# ESP32CAM-Motorhat.net
KiCad netlist of a schematic drawn in EAGLE
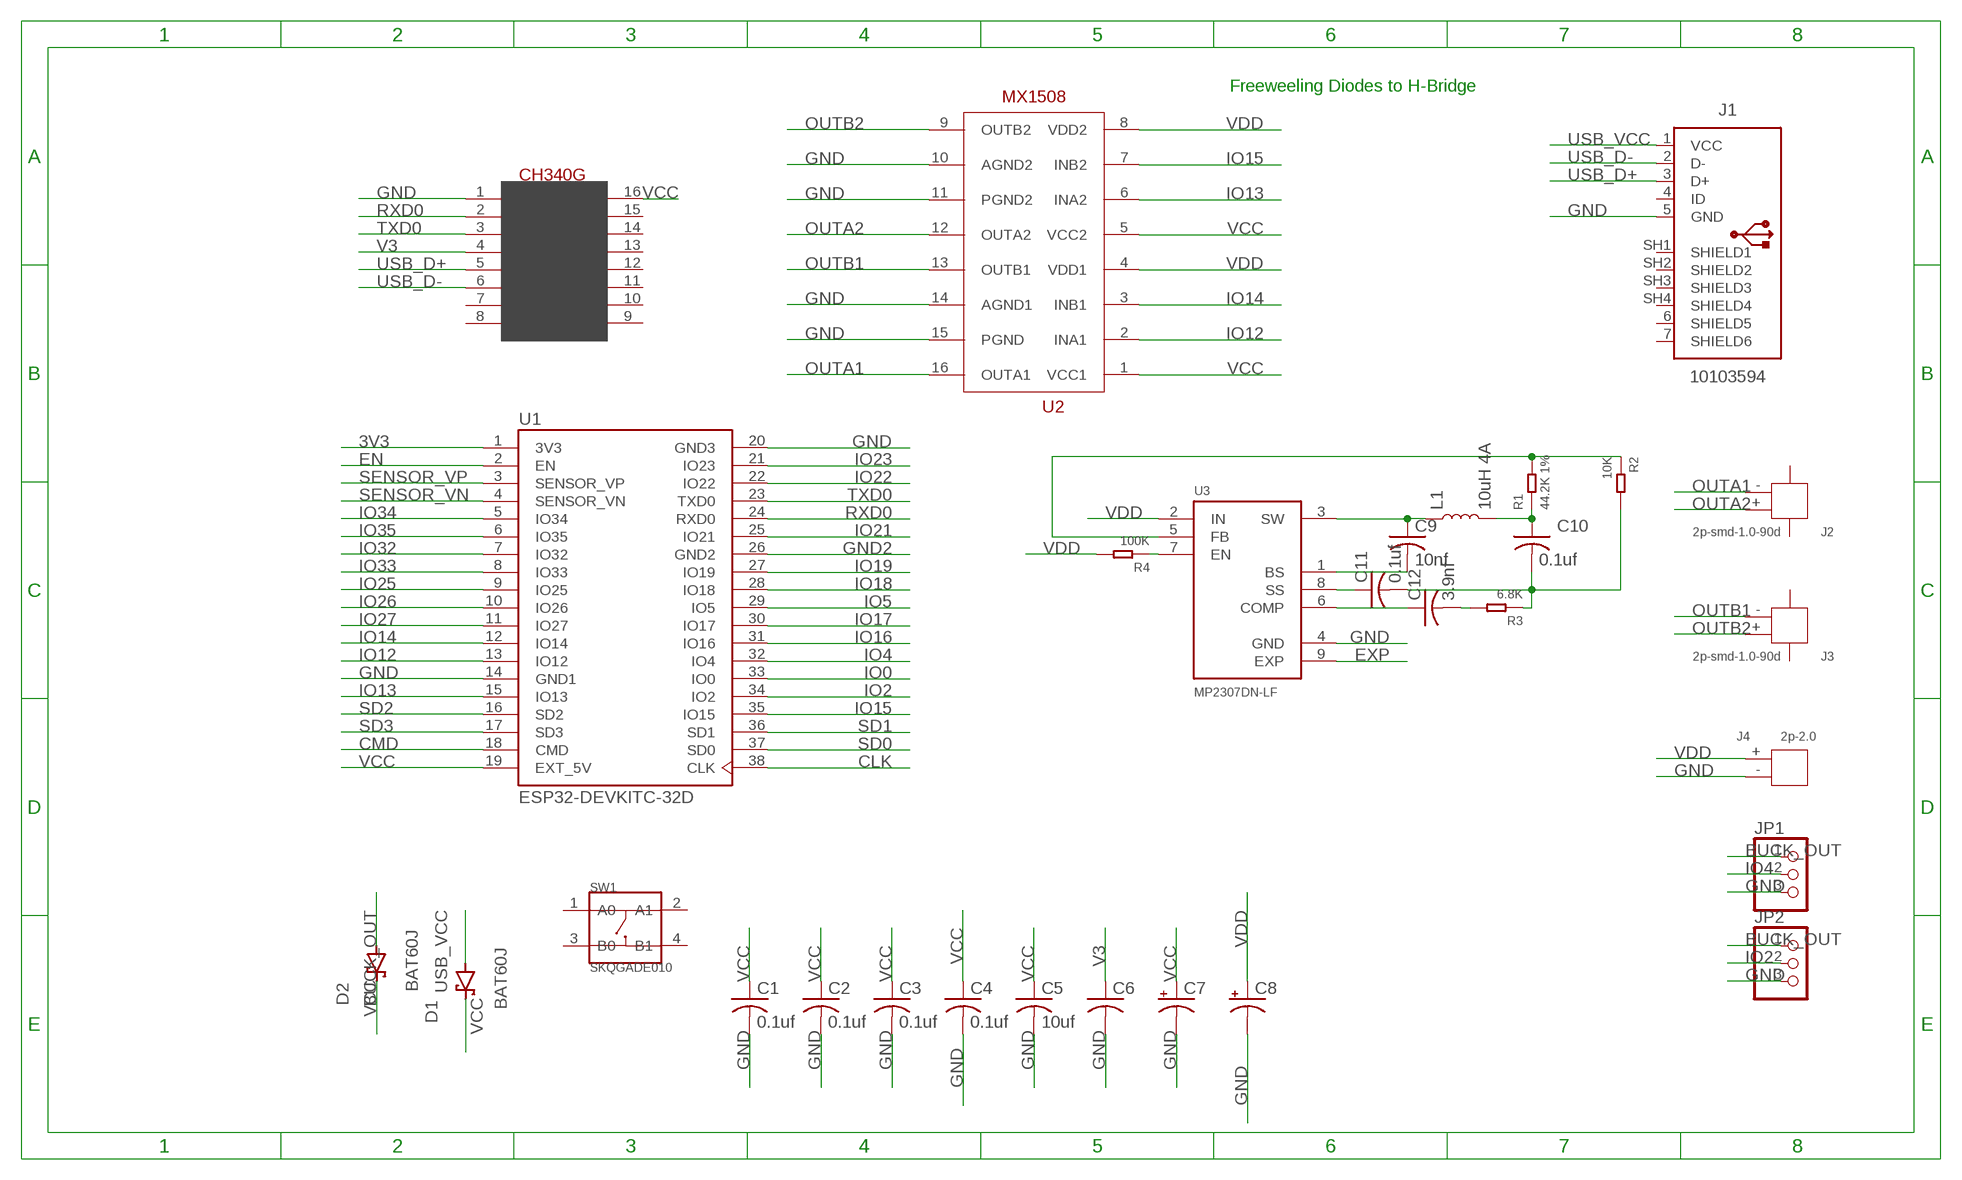
[diagram p0: schematic, sheet 1]

(export (version "E")
  (design (tool "Eeschema 10.0.6"))
  (components
    (comp (ref "C1")
      (value "0.1uf")
      (footprint "eagle-import:C1206")
      (libsource (lib "eagle-import") (part "C-USC1206"))
    )
    (comp (ref "C2")
      (value "0.1uf")
      (footprint "eagle-import:C1206")
      (libsource (lib "eagle-import") (part "C-USC1206"))
    )
    (comp (ref "C3")
      (value "0.1uf")
      (footprint "eagle-import:C1206")
      (libsource (lib "eagle-import") (part "C-USC1206"))
    )
    (comp (ref "C4")
      (value "0.1uf")
      (footprint "eagle-import:C1206")
      (libsource (lib "eagle-import") (part "C-USC1206"))
    )
    (comp (ref "C5")
      (value "10uf")
      (footprint "eagle-import:C1206")
      (libsource (lib "eagle-import") (part "C-USC1206"))
    )
    (comp (ref "C6")
      (value "C-USC1206")
      (footprint "eagle-import:C1206")
      (libsource (lib "eagle-import") (part "C-USC1206"))
    )
    (comp (ref "C7")
      (value "CPOL-USD")
      (footprint "eagle-import:PANASONIC_D")
      (libsource (lib "eagle-import") (part "CPOL-USD"))
    )
    (comp (ref "C8")
      (value "CPOL-USD")
      (footprint "eagle-import:PANASONIC_D")
      (libsource (lib "eagle-import") (part "CPOL-USD"))
    )
    (comp (ref "C9")
      (value "10nf")
      (footprint "eagle-import:C1206")
      (libsource (lib "eagle-import") (part "C-USC1206"))
    )
    (comp (ref "C10")
      (value "0.1uf")
      (footprint "eagle-import:C1206")
      (libsource (lib "eagle-import") (part "C-USC1206"))
    )
    (comp (ref "C11")
      (value "0.1uf")
      (footprint "eagle-import:C1206")
      (libsource (lib "eagle-import") (part "C-USC1206"))
    )
    (comp (ref "C12")
      (value "3.9nf")
      (footprint "eagle-import:C1206")
      (libsource (lib "eagle-import") (part "C-USC1206"))
    )
    (comp (ref "D1")
      (value "BAT60J")
      (footprint "eagle-import:SOD323_ST")
      (libsource (lib "eagle-import") (part "BAT60J"))
    )
    (comp (ref "D2")
      (value "BAT60J")
      (footprint "eagle-import:SOD323_ST")
      (libsource (lib "eagle-import") (part "BAT60J"))
    )
    (comp (ref "J1")
      (value "10103594")
      (footprint "eagle-import:10103594")
      (fields (field (name "MANUFACTURER") "Amphenol ICC (FCI)") (field (name "MPN") "10103594-0001LF"))
      (libsource (lib "eagle-import") (part "10103594"))
    )
    (comp (ref "J2")
      (value "2p-smd-1.0-90d")
      (footprint "eagle-import:HW2-SMD-1.0-90D")
      (libsource (lib "eagle-import") (part "SMD-JST-2P-1.0-90D"))
    )
    (comp (ref "J3")
      (value "2p-smd-1.0-90d")
      (footprint "eagle-import:HW2-SMD-1.0-90D")
      (libsource (lib "eagle-import") (part "SMD-JST-2P-1.0-90D"))
    )
    (comp (ref "J4")
      (value "2p-2.0")
      (footprint "eagle-import:H2-2.0-6X4.5MM")
      (fields (field (name "SPICEPREFIX") "B"))
      (libsource (lib "eagle-import") (part "DIP-JST-2P-2.0"))
    )
    (comp (ref "JP1")
      (value "PINHD-1X3CB")
      (footprint "eagle-import:1X03-CLEANBIG")
      (libsource (lib "eagle-import") (part "PINHD-1X3CB"))
    )
    (comp (ref "JP2")
      (value "PINHD-1X3CB")
      (footprint "eagle-import:1X03-CLEANBIG")
      (libsource (lib "eagle-import") (part "PINHD-1X3CB"))
    )
    (comp (ref "L1")
      (value "10uH 4A")
      (footprint "eagle-import:0402_MURATA")
      (libsource (lib "eagle-import") (part "19NH-0402"))
    )
    (comp (ref "R1")
      (value "44.2K 1%")
      (footprint "eagle-import:R0805")
      (fields (field (name "MPN") "RC0805JR-071KL"))
      (libsource (lib "eagle-import") (part "SMD-RES-0R-1%-1/8W(0805)"))
    )
    (comp (ref "R2")
      (value "10K")
      (footprint "eagle-import:R0805")
      (fields (field (name "MPN") "RC0805JR-071KL"))
      (libsource (lib "eagle-import") (part "SMD-RES-0R-1%-1/8W(0805)"))
    )
    (comp (ref "R3")
      (value "6.8K")
      (footprint "eagle-import:R0805")
      (fields (field (name "MPN") "RC0805JR-071KL"))
      (libsource (lib "eagle-import") (part "SMD-RES-0R-1%-1/8W(0805)"))
    )
    (comp (ref "R4")
      (value "100K")
      (footprint "eagle-import:R0805")
      (fields (field (name "MPN") "RC0805JR-071KL"))
      (libsource (lib "eagle-import") (part "SMD-RES-0R-1%-1/8W(0805)"))
    )
    (comp (ref "SW1")
      (value "SKQGADE010")
      (footprint "eagle-import:SW4-SMD-5.2X5.2X1.5MM")
      (libsource (lib "eagle-import") (part "SMD-BUTTON(4P-5.2X5.2X1.5MM-SKQGADE010)-SKQGADE010"))
    )
    (comp (ref "U1")
      (value "ESP32-DEVKITC-32D")
      (footprint "eagle-import:MODULE_ESP32-DEVKITC-32D")
      (fields (field (name "MF") "Espressif Systems"))
      (libsource (lib "eagle-import") (part "ESP32-DEVKITC-32D"))
    )
    (comp (ref "U2")
      (value "MX1508")
      (footprint "eagle-import:SOP-16")
      (fields (field (name "MF") "Sinotech Mixic Electronics Co., Ltd"))
      (libsource (lib "eagle-import") (part "MX1508"))
    )
    (comp (ref "U3")
      (value "MP2307DN-LF")
      (footprint "eagle-import:SOIC127P600X170-9N")
      (fields (field (name "MF") "Monolithic Power"))
      (libsource (lib "eagle-import") (part "MP2307DN-LF"))
    )
    (comp (ref "U4")
      (value "CH340G")
      (footprint "eagle-import:SOIC16")
      (libsource (lib "eagle-import") (part "CH340G"))
    )
  )
  (nets
    (net (code "1") (name "/3V3") (class "Default")
      (node (ref "U1") (pin "1") (pinfunction "3V3_1") (pintype "power_in"))
    )
    (net (code "2") (name "/BUCK_OUT") (class "Default")
      (node (ref "C10") (pin "1") (pinfunction "1_1") (pintype "passive"))
      (node (ref "D2") (pin "A") (pinfunction "A_A") (pintype "passive"))
      (node (ref "JP1") (pin "1") (pinfunction "1_1") (pintype "passive"))
      (node (ref "JP2") (pin "1") (pinfunction "1_1") (pintype "passive"))
      (node (ref "L1") (pin "P$2") (pinfunction "2_P$2") (pintype "passive"))
      (node (ref "R1") (pin "1") (pinfunction "1_1") (pintype "passive"))
    )
    (net (code "3") (name "/CLK") (class "Default")
      (node (ref "U1") (pin "38") (pinfunction "CLK_38") (pintype "input"))
    )
    (net (code "4") (name "/CMD") (class "Default")
      (node (ref "U1") (pin "18") (pinfunction "CMD_18") (pintype "bidirectional"))
    )
    (net (code "5") (name "/EN") (class "Default")
      (node (ref "U1") (pin "2") (pinfunction "EN_2") (pintype "input"))
    )
    (net (code "6") (name "/EXP") (class "Default")
      (node (ref "U3") (pin "9") (pinfunction "EXP_9") (pintype "power_in"))
    )
    (net (code "7") (name "/GND") (class "Default")
      (node (ref "C1") (pin "2") (pinfunction "2_2") (pintype "passive"))
      (node (ref "C2") (pin "2") (pinfunction "2_2") (pintype "passive"))
      (node (ref "C3") (pin "2") (pinfunction "2_2") (pintype "passive"))
      (node (ref "C4") (pin "2") (pinfunction "2_2") (pintype "passive"))
      (node (ref "C5") (pin "2") (pinfunction "2_2") (pintype "passive"))
      (node (ref "C6") (pin "2") (pinfunction "2_2") (pintype "passive"))
      (node (ref "C7") (pin "-") (pinfunction "-_-") (pintype "passive"))
      (node (ref "C8") (pin "-") (pinfunction "-_-") (pintype "passive"))
      (node (ref "J1") (pin "5") (pinfunction "GND_5") (pintype "power_in"))
      (node (ref "J4") (pin "-") (pinfunction "P$2_-") (pintype "bidirectional"))
      (node (ref "JP1") (pin "3") (pinfunction "3_3") (pintype "passive"))
      (node (ref "JP2") (pin "3") (pinfunction "3_3") (pintype "passive"))
      (node (ref "U1") (pin "14") (pinfunction "GND1_14") (pintype "power_in"))
      (node (ref "U1") (pin "20") (pinfunction "GND3_20") (pintype "power_in"))
      (node (ref "U2") (pin "10") (pinfunction "AGND2_10") (pintype "bidirectional"))
      (node (ref "U2") (pin "11") (pinfunction "PGND2_11") (pintype "bidirectional"))
      (node (ref "U2") (pin "14") (pinfunction "AGND1_14") (pintype "bidirectional"))
      (node (ref "U2") (pin "15") (pinfunction "PGND_15") (pintype "bidirectional"))
      (node (ref "U3") (pin "4") (pinfunction "GND_4") (pintype "power_in"))
      (node (ref "U4") (pin "1") (pinfunction "GND_1") (pintype "bidirectional"))
    )
    (net (code "8") (name "/GND2") (class "Default")
      (node (ref "U1") (pin "26") (pinfunction "GND2_26") (pintype "power_in"))
    )
    (net (code "9") (name "/IO0") (class "Default")
      (node (ref "U1") (pin "33") (pinfunction "IO0_33") (pintype "bidirectional"))
    )
    (net (code "10") (name "/IO2") (class "Default")
      (node (ref "JP2") (pin "2") (pinfunction "2_2") (pintype "passive"))
      (node (ref "U1") (pin "34") (pinfunction "IO2_34") (pintype "bidirectional"))
    )
    (net (code "11") (name "/IO4") (class "Default")
      (node (ref "JP1") (pin "2") (pinfunction "2_2") (pintype "passive"))
      (node (ref "U1") (pin "32") (pinfunction "IO4_32") (pintype "bidirectional"))
    )
    (net (code "12") (name "/IO5") (class "Default")
      (node (ref "U1") (pin "29") (pinfunction "IO5_29") (pintype "bidirectional"))
    )
    (net (code "13") (name "/IO12") (class "Default")
      (node (ref "U1") (pin "13") (pinfunction "IO12_13") (pintype "bidirectional"))
      (node (ref "U2") (pin "2") (pinfunction "INA1_2") (pintype "bidirectional"))
    )
    (net (code "14") (name "/IO13") (class "Default")
      (node (ref "U1") (pin "15") (pinfunction "IO13_15") (pintype "bidirectional"))
      (node (ref "U2") (pin "6") (pinfunction "INA2_6") (pintype "bidirectional"))
    )
    (net (code "15") (name "/IO14") (class "Default")
      (node (ref "U1") (pin "12") (pinfunction "IO14_12") (pintype "bidirectional"))
      (node (ref "U2") (pin "3") (pinfunction "INB1_3") (pintype "bidirectional"))
    )
    (net (code "16") (name "/IO15") (class "Default")
      (node (ref "U1") (pin "35") (pinfunction "IO15_35") (pintype "bidirectional"))
      (node (ref "U2") (pin "7") (pinfunction "INB2_7") (pintype "bidirectional"))
    )
    (net (code "17") (name "/IO16") (class "Default")
      (node (ref "U1") (pin "31") (pinfunction "IO16_31") (pintype "bidirectional"))
    )
    (net (code "18") (name "/IO17") (class "Default")
      (node (ref "U1") (pin "30") (pinfunction "IO17_30") (pintype "bidirectional"))
    )
    (net (code "19") (name "/IO18") (class "Default")
      (node (ref "U1") (pin "28") (pinfunction "IO18_28") (pintype "bidirectional"))
    )
    (net (code "20") (name "/IO19") (class "Default")
      (node (ref "U1") (pin "27") (pinfunction "IO19_27") (pintype "bidirectional"))
    )
    (net (code "21") (name "/IO21") (class "Default")
      (node (ref "U1") (pin "25") (pinfunction "IO21_25") (pintype "bidirectional"))
    )
    (net (code "22") (name "/IO22") (class "Default")
      (node (ref "U1") (pin "22") (pinfunction "IO22_22") (pintype "bidirectional"))
    )
    (net (code "23") (name "/IO23") (class "Default")
      (node (ref "U1") (pin "21") (pinfunction "IO23_21") (pintype "bidirectional"))
    )
    (net (code "24") (name "/IO25") (class "Default")
      (node (ref "U1") (pin "9") (pinfunction "IO25_9") (pintype "bidirectional"))
    )
    (net (code "25") (name "/IO26") (class "Default")
      (node (ref "U1") (pin "10") (pinfunction "IO26_10") (pintype "bidirectional"))
    )
    (net (code "26") (name "/IO27") (class "Default")
      (node (ref "U1") (pin "11") (pinfunction "IO27_11") (pintype "bidirectional"))
    )
    (net (code "27") (name "/IO32") (class "Default")
      (node (ref "U1") (pin "7") (pinfunction "IO32_7") (pintype "bidirectional"))
    )
    (net (code "28") (name "/IO33") (class "Default")
      (node (ref "U1") (pin "8") (pinfunction "IO33_8") (pintype "bidirectional"))
    )
    (net (code "29") (name "/IO34") (class "Default")
      (node (ref "U1") (pin "5") (pinfunction "IO34_5") (pintype "bidirectional"))
    )
    (net (code "30") (name "/IO35") (class "Default")
      (node (ref "U1") (pin "6") (pinfunction "IO35_6") (pintype "bidirectional"))
    )
    (net (code "31") (name "/OUTA1") (class "Default")
      (node (ref "J2") (pin "-") (pinfunction "2_-") (pintype "bidirectional"))
      (node (ref "U2") (pin "16") (pinfunction "OUTA1_16") (pintype "bidirectional"))
    )
    (net (code "32") (name "/OUTA2") (class "Default")
      (node (ref "J2") (pin "+") (pinfunction "1_+") (pintype "bidirectional"))
      (node (ref "U2") (pin "12") (pinfunction "OUTA2_12") (pintype "bidirectional"))
    )
    (net (code "33") (name "/OUTB1") (class "Default")
      (node (ref "J3") (pin "-") (pinfunction "2_-") (pintype "bidirectional"))
      (node (ref "U2") (pin "13") (pinfunction "OUTB1_13") (pintype "bidirectional"))
    )
    (net (code "34") (name "/OUTB2") (class "Default")
      (node (ref "J3") (pin "+") (pinfunction "1_+") (pintype "bidirectional"))
      (node (ref "U2") (pin "9") (pinfunction "OUTB2_9") (pintype "bidirectional"))
    )
    (net (code "35") (name "/RXD0") (class "Default")
      (node (ref "U1") (pin "24") (pinfunction "RXD0_24") (pintype "input"))
      (node (ref "U4") (pin "2") (pinfunction "TX_2") (pintype "bidirectional"))
    )
    (net (code "36") (name "/SD0") (class "Default")
      (node (ref "U1") (pin "37") (pinfunction "SD0_37") (pintype "bidirectional"))
    )
    (net (code "37") (name "/SD1") (class "Default")
      (node (ref "U1") (pin "36") (pinfunction "SD1_36") (pintype "bidirectional"))
    )
    (net (code "38") (name "/SD2") (class "Default")
      (node (ref "U1") (pin "16") (pinfunction "SD2_16") (pintype "bidirectional"))
    )
    (net (code "39") (name "/SD3") (class "Default")
      (node (ref "U1") (pin "17") (pinfunction "SD3_17") (pintype "bidirectional"))
    )
    (net (code "40") (name "/SENSOR_VN") (class "Default")
      (node (ref "U1") (pin "4") (pinfunction "SENSOR_VN_4") (pintype "input"))
    )
    (net (code "41") (name "/SENSOR_VP") (class "Default")
      (node (ref "U1") (pin "3") (pinfunction "SENSOR_VP_3") (pintype "input"))
    )
    (net (code "42") (name "/SHIELD1") (class "Default")
      (node (ref "J1") (pin "SH1") (pinfunction "SHIELD1_SH1") (pintype "power_in"))
    )
    (net (code "43") (name "/SHIELD2") (class "Default")
      (node (ref "J1") (pin "SH2") (pinfunction "SHIELD2_SH2") (pintype "power_in"))
    )
    (net (code "44") (name "/SHIELD3") (class "Default")
      (node (ref "J1") (pin "SH3") (pinfunction "SHIELD3_SH3") (pintype "power_in"))
    )
    (net (code "45") (name "/SHIELD4") (class "Default")
      (node (ref "J1") (pin "SH4") (pinfunction "SHIELD4_SH4") (pintype "power_in"))
    )
    (net (code "46") (name "/SHIELD5") (class "Default")
      (node (ref "J1") (pin "6") (pinfunction "SHIELD5_6") (pintype "power_in"))
    )
    (net (code "47") (name "/SHIELD6") (class "Default")
      (node (ref "J1") (pin "7") (pinfunction "SHIELD6_7") (pintype "power_in"))
    )
    (net (code "48") (name "/TXD0") (class "Default")
      (node (ref "U1") (pin "23") (pinfunction "TXD0_23") (pintype "output"))
      (node (ref "U4") (pin "3") (pinfunction "RX_3") (pintype "bidirectional"))
    )
    (net (code "49") (name "/USB_D+") (class "Default")
      (node (ref "J1") (pin "3") (pinfunction "D+_3") (pintype "bidirectional"))
      (node (ref "U4") (pin "5") (pinfunction "D+_5") (pintype "bidirectional"))
    )
    (net (code "50") (name "/USB_D-") (class "Default")
      (node (ref "J1") (pin "2") (pinfunction "D-_2") (pintype "bidirectional"))
      (node (ref "U4") (pin "6") (pinfunction "D-_6") (pintype "bidirectional"))
    )
    (net (code "51") (name "/USB_VCC") (class "Default")
      (node (ref "D1") (pin "A") (pinfunction "A_A") (pintype "passive"))
      (node (ref "J1") (pin "1") (pinfunction "VCC_1") (pintype "power_in"))
    )
    (net (code "52") (name "/V3") (class "Default")
      (node (ref "C6") (pin "1") (pinfunction "1_1") (pintype "passive"))
      (node (ref "U4") (pin "4") (pinfunction "V3_4") (pintype "bidirectional"))
    )
    (net (code "53") (name "/VCC") (class "Default")
      (node (ref "C1") (pin "1") (pinfunction "1_1") (pintype "passive"))
      (node (ref "C2") (pin "1") (pinfunction "1_1") (pintype "passive"))
      (node (ref "C3") (pin "1") (pinfunction "1_1") (pintype "passive"))
      (node (ref "C4") (pin "1") (pinfunction "1_1") (pintype "passive"))
      (node (ref "C5") (pin "1") (pinfunction "1_1") (pintype "passive"))
      (node (ref "C7") (pin "+") (pinfunction "+_+") (pintype "passive"))
      (node (ref "D1") (pin "C") (pinfunction "C_C") (pintype "passive"))
      (node (ref "D2") (pin "C") (pinfunction "C_C") (pintype "passive"))
      (node (ref "U1") (pin "19") (pinfunction "EXT_5V_19") (pintype "power_in"))
      (node (ref "U2") (pin "1") (pinfunction "VCC1_1") (pintype "bidirectional"))
      (node (ref "U2") (pin "5") (pinfunction "VCC2_5") (pintype "bidirectional"))
      (node (ref "U4") (pin "16") (pinfunction "VCC_16") (pintype "bidirectional"))
    )
    (net (code "54") (name "/VDD") (class "Default")
      (node (ref "C8") (pin "+") (pinfunction "+_+") (pintype "passive"))
      (node (ref "J4") (pin "+") (pinfunction "P$1_+") (pintype "bidirectional"))
      (node (ref "R4") (pin "2") (pinfunction "2_2") (pintype "passive"))
      (node (ref "U2") (pin "4") (pinfunction "VDD1_4") (pintype "bidirectional"))
      (node (ref "U2") (pin "8") (pinfunction "VDD2_8") (pintype "bidirectional"))
      (node (ref "U3") (pin "2") (pinfunction "IN_2") (pintype "input"))
    )
    (net (code "55") (name "Net-(C10-Pad2)") (class "Default")
      (node (ref "C10") (pin "2") (pinfunction "2_2") (pintype "passive"))
      (node (ref "C11") (pin "2") (pinfunction "2_2") (pintype "passive"))
      (node (ref "R2") (pin "2") (pinfunction "2_2") (pintype "passive"))
      (node (ref "R3") (pin "1") (pinfunction "1_1") (pintype "passive"))
    )
    (net (code "56") (name "Net-(C12-Pad2)") (class "Default")
      (node (ref "C12") (pin "2") (pinfunction "2_2") (pintype "passive"))
      (node (ref "R3") (pin "2") (pinfunction "2_2") (pintype "passive"))
    )
    (net (code "57") (name "Net-(L1-1)") (class "Default")
      (node (ref "C9") (pin "1") (pinfunction "1_1") (pintype "passive"))
      (node (ref "L1") (pin "P$1") (pinfunction "1_P$1") (pintype "passive"))
      (node (ref "U3") (pin "3") (pinfunction "SW_3") (pintype "output"))
    )
    (net (code "58") (name "Net-(U3-BS)") (class "Default")
      (node (ref "C9") (pin "2") (pinfunction "2_2") (pintype "passive"))
      (node (ref "U3") (pin "1") (pinfunction "BS_1") (pintype "passive"))
    )
    (net (code "59") (name "Net-(U3-COMP)") (class "Default")
      (node (ref "C12") (pin "1") (pinfunction "1_1") (pintype "passive"))
      (node (ref "U3") (pin "6") (pinfunction "COMP_6") (pintype "passive"))
    )
    (net (code "60") (name "Net-(U3-EN)") (class "Default")
      (node (ref "R4") (pin "1") (pinfunction "1_1") (pintype "passive"))
      (node (ref "U3") (pin "7") (pinfunction "EN_7") (pintype "input"))
    )
    (net (code "61") (name "Net-(U3-FB)") (class "Default")
      (node (ref "R1") (pin "2") (pinfunction "2_2") (pintype "passive"))
      (node (ref "R2") (pin "1") (pinfunction "1_1") (pintype "passive"))
      (node (ref "U3") (pin "5") (pinfunction "FB_5") (pintype "input"))
    )
    (net (code "62") (name "Net-(U3-SS)") (class "Default")
      (node (ref "C11") (pin "1") (pinfunction "1_1") (pintype "passive"))
      (node (ref "U3") (pin "8") (pinfunction "SS_8") (pintype "passive"))
    )
    (net (code "63") (name "unconnected-(J1-ID-Pad4)") (class "Default")
      (node (ref "J1") (pin "4") (pinfunction "ID_4") (pintype "bidirectional"))
    )
    (net (code "64") (name "unconnected-(J2-Pad3)") (class "Default")
      (node (ref "J2") (pin "3") (pinfunction "3_3") (pintype "bidirectional"))
    )
    (net (code "65") (name "unconnected-(J2-Pad4)") (class "Default")
      (node (ref "J2") (pin "4") (pinfunction "4_4") (pintype "bidirectional"))
    )
    (net (code "66") (name "unconnected-(J3-Pad3)") (class "Default")
      (node (ref "J3") (pin "3") (pinfunction "3_3") (pintype "bidirectional"))
    )
    (net (code "67") (name "unconnected-(J3-Pad4)") (class "Default")
      (node (ref "J3") (pin "4") (pinfunction "4_4") (pintype "bidirectional"))
    )
    (net (code "68") (name "unconnected-(SW1-A0-Pad1)") (class "Default")
      (node (ref "SW1") (pin "1") (pinfunction "A0_1") (pintype "bidirectional"))
    )
    (net (code "69") (name "unconnected-(SW1-A1-Pad2)") (class "Default")
      (node (ref "SW1") (pin "2") (pinfunction "A1_2") (pintype "bidirectional"))
    )
    (net (code "70") (name "unconnected-(SW1-B0-Pad3)") (class "Default")
      (node (ref "SW1") (pin "3") (pinfunction "B0_3") (pintype "bidirectional"))
    )
    (net (code "71") (name "unconnected-(SW1-B1-Pad4)") (class "Default")
      (node (ref "SW1") (pin "4") (pinfunction "B1_4") (pintype "bidirectional"))
    )
    (net (code "72") (name "unconnected-(U4-CTS-Pad9)") (class "Default")
      (node (ref "U4") (pin "9") (pinfunction "CTS_9") (pintype "bidirectional"))
    )
    (net (code "73") (name "unconnected-(U4-DCD-Pad12)") (class "Default")
      (node (ref "U4") (pin "12") (pinfunction "DCD_12") (pintype "bidirectional"))
    )
    (net (code "74") (name "unconnected-(U4-DSR-Pad10)") (class "Default")
      (node (ref "U4") (pin "10") (pinfunction "DSR_10") (pintype "bidirectional"))
    )
    (net (code "75") (name "unconnected-(U4-DTR-Pad13)") (class "Default")
      (node (ref "U4") (pin "13") (pinfunction "DTR_13") (pintype "bidirectional"))
    )
    (net (code "76") (name "unconnected-(U4-RI-Pad11)") (class "Default")
      (node (ref "U4") (pin "11") (pinfunction "RI_11") (pintype "bidirectional"))
    )
    (net (code "77") (name "unconnected-(U4-RS232-Pad15)") (class "Default")
      (node (ref "U4") (pin "15") (pinfunction "RS232_15") (pintype "bidirectional"))
    )
    (net (code "78") (name "unconnected-(U4-RTS-Pad14)") (class "Default")
      (node (ref "U4") (pin "14") (pinfunction "RTS_14") (pintype "bidirectional"))
    )
    (net (code "79") (name "unconnected-(U4-XI-Pad7)") (class "Default")
      (node (ref "U4") (pin "7") (pinfunction "XI_7") (pintype "bidirectional"))
    )
    (net (code "80") (name "unconnected-(U4-XO-Pad8)") (class "Default")
      (node (ref "U4") (pin "8") (pinfunction "XO_8") (pintype "bidirectional"))
    )
  )
)
